# DAC.net
KiCad netlist of a schematic drawn in EAGLE
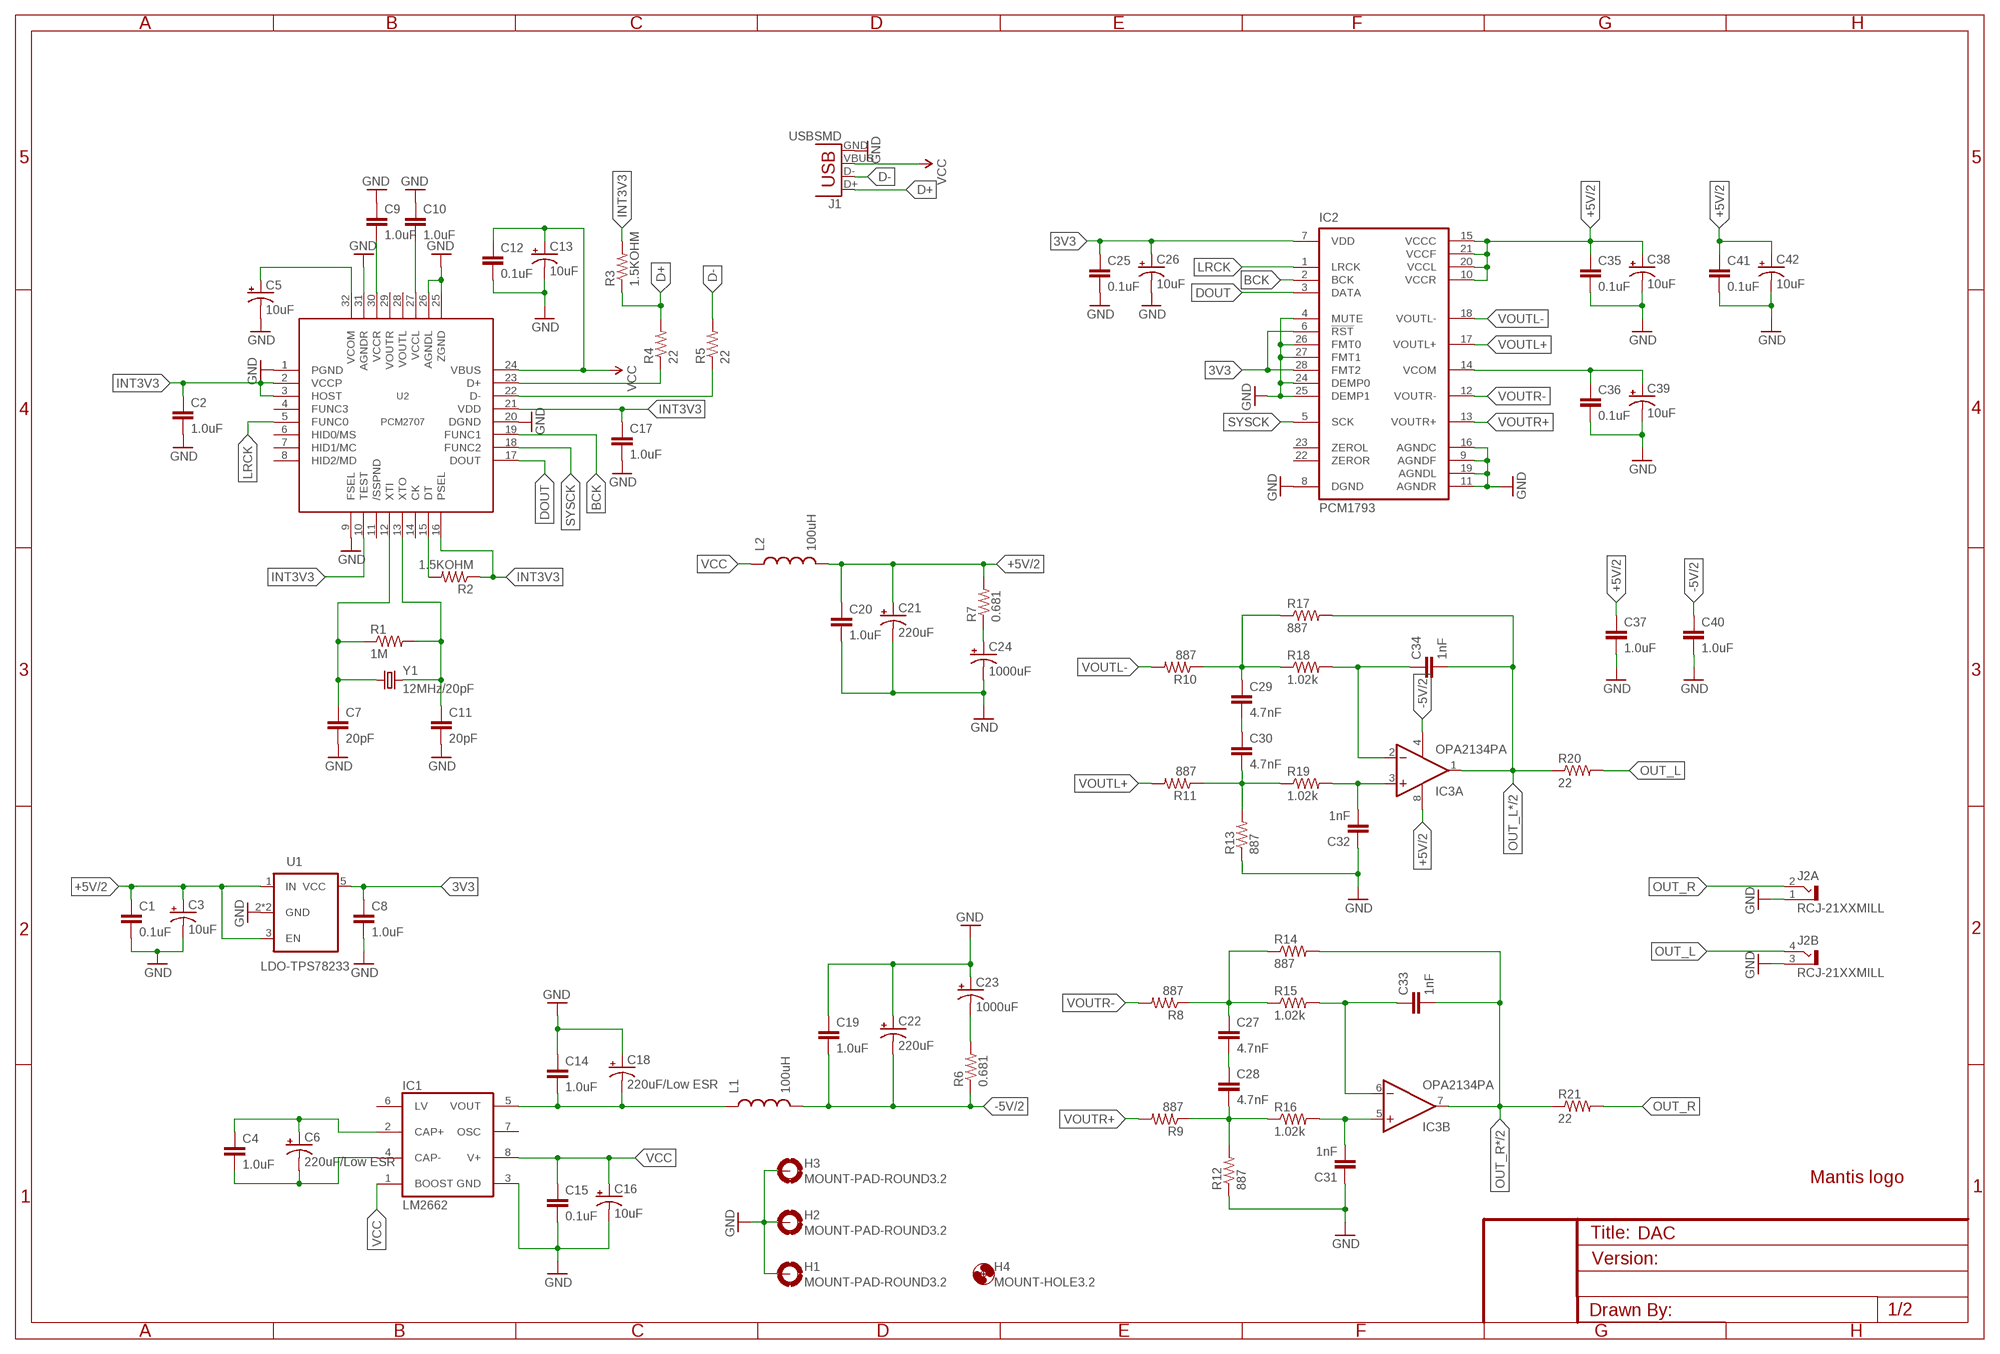
[diagram p0: schematic, sheet 1]
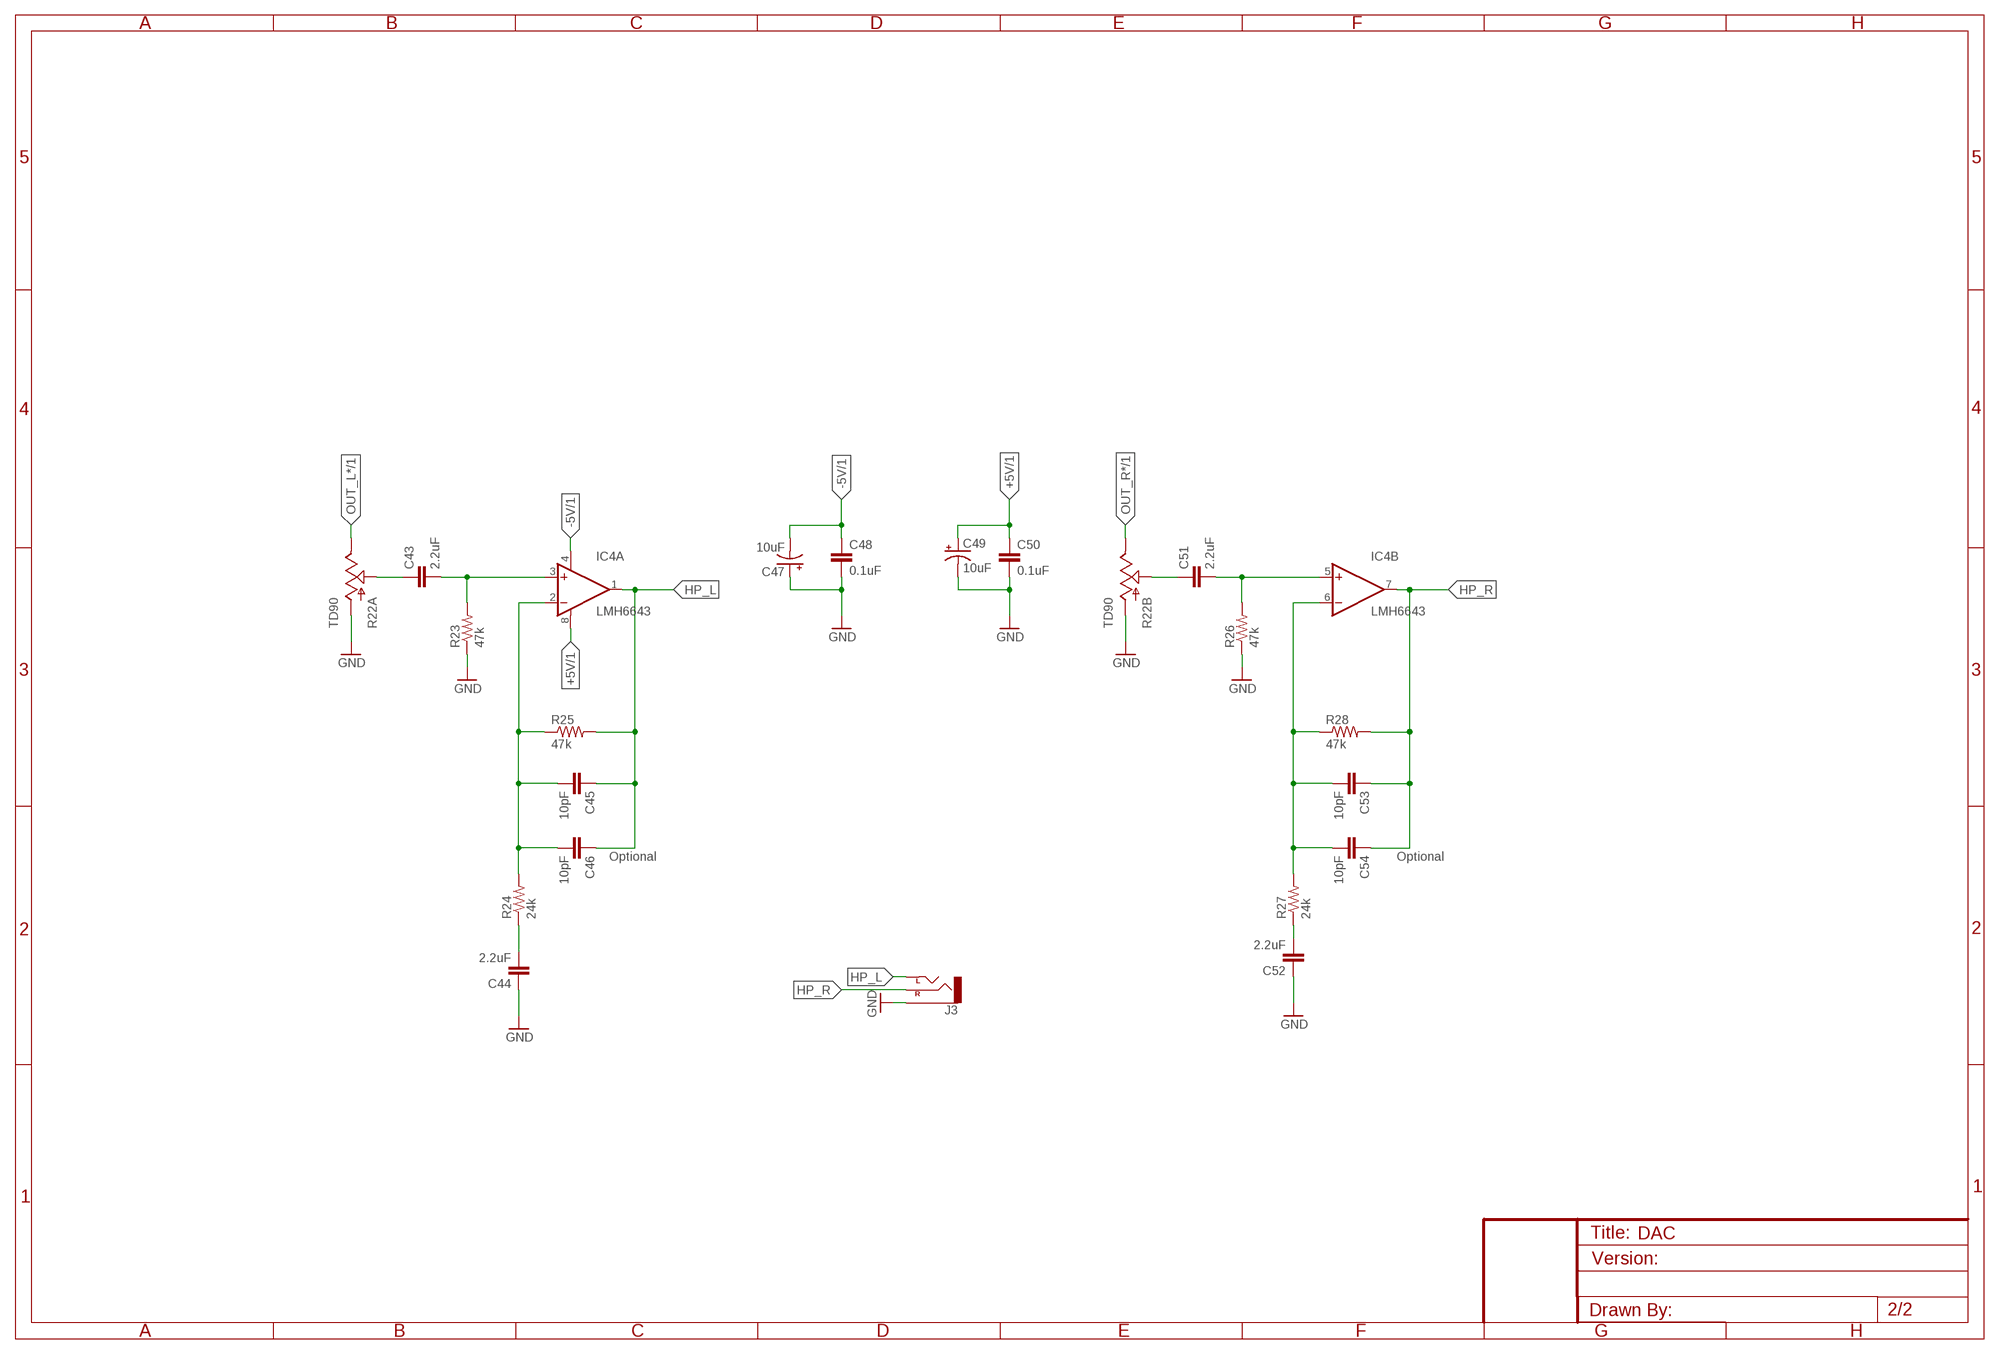
[diagram p1: schematic, sheet 2]

(export (version "E")
  (design (tool "Eeschema 10.0.6"))
  (components
    (comp (ref "C43")
      (value "2.2uF")
      (footprint "eagle-import:C5B5")
      (libsource (lib "eagle-import") (part "C5/5"))
    )
    (comp (ref "C44")
      (value "2.2uF")
      (footprint "eagle-import:C5B5")
      (libsource (lib "eagle-import") (part "C5/5"))
    )
    (comp (ref "C45")
      (value "10pF")
      (footprint "eagle-import:CAP-PTH-SMALL")
      (libsource (lib "eagle-import") (part "CAPPTH"))
    )
    (comp (ref "C46")
      (value "10pF")
      (footprint "eagle-import:0603-CAP")
      (libsource (lib "eagle-import") (part "10PF-50V-5%(0603)"))
    )
    (comp (ref "C47")
      (value "10uF")
      (footprint "eagle-import:CPOL-RADIAL-10UF-25V")
      (libsource (lib "eagle-import") (part "CAP_POLPTH2"))
    )
    (comp (ref "C48")
      (value "0.1uF")
      (footprint "eagle-import:0603-CAP")
      (libsource (lib "eagle-import") (part "1.0UF-16V-10%(0603)"))
    )
    (comp (ref "C49")
      (value "10uF")
      (footprint "eagle-import:CPOL-RADIAL-10UF-25V")
      (libsource (lib "eagle-import") (part "CAP_POLPTH2"))
    )
    (comp (ref "C50")
      (value "0.1uF")
      (footprint "eagle-import:0603-CAP")
      (libsource (lib "eagle-import") (part "1.0UF-16V-10%(0603)"))
    )
    (comp (ref "C51")
      (value "2.2uF")
      (footprint "eagle-import:C5B5")
      (libsource (lib "eagle-import") (part "C5/5"))
    )
    (comp (ref "C52")
      (value "2.2uF")
      (footprint "eagle-import:C5B5")
      (libsource (lib "eagle-import") (part "C5/5"))
    )
    (comp (ref "C53")
      (value "10pF")
      (footprint "eagle-import:CAP-PTH-SMALL")
      (libsource (lib "eagle-import") (part "CAPPTH"))
    )
    (comp (ref "C54")
      (value "10pF")
      (footprint "eagle-import:0603-CAP")
      (libsource (lib "eagle-import") (part "10PF-50V-5%(0603)"))
    )
    (comp (ref "IC4")
      (value "LMH6643")
      (footprint "eagle-import:SO08")
      (libsource (lib "eagle-import") (part "LMH6643"))
    )
    (comp (ref "J3")
      (value "AUDIO-JACKPTH")
      (footprint "eagle-import:AUDIO-JACK")
      (libsource (lib "eagle-import") (part "AUDIO-JACKPTH"))
    )
    (comp (ref "R22")
      (value "TD90")
      (footprint "eagle-import:PTD902")
      (libsource (lib "eagle-import") (part "TD90"))
    )
    (comp (ref "R23")
      (value "47k")
      (footprint "eagle-import:AXIAL-0.4")
      (libsource (lib "eagle-import") (part "RESISTORPTH-1/4W"))
    )
    (comp (ref "R24")
      (value "24k")
      (footprint "eagle-import:AXIAL-0.4")
      (libsource (lib "eagle-import") (part "RESISTORPTH-1/4W"))
    )
    (comp (ref "R25")
      (value "47k")
      (footprint "eagle-import:AXIAL-0.4")
      (libsource (lib "eagle-import") (part "RESISTORPTH-1/4W"))
    )
    (comp (ref "R26")
      (value "47k")
      (footprint "eagle-import:AXIAL-0.4")
      (libsource (lib "eagle-import") (part "RESISTORPTH-1/4W"))
    )
    (comp (ref "R27")
      (value "24k")
      (footprint "eagle-import:AXIAL-0.4")
      (libsource (lib "eagle-import") (part "RESISTORPTH-1/4W"))
    )
    (comp (ref "R28")
      (value "47k")
      (footprint "eagle-import:AXIAL-0.4")
      (libsource (lib "eagle-import") (part "RESISTORPTH-1/4W"))
    )
    (comp (ref "C1")
      (value "0.1uF")
      (footprint "eagle-import:0603-CAP")
      (libsource (lib "eagle-import") (part "0.1UF-25V-5%(0603)"))
    )
    (comp (ref "C2")
      (value "1.0uF")
      (footprint "eagle-import:0603-CAP")
      (libsource (lib "eagle-import") (part "1.0UF-16V-10%(0603)"))
    )
    (comp (ref "C3")
      (value "10uF")
      (footprint "eagle-import:CPOL-RADIAL-10UF-25V")
      (libsource (lib "eagle-import") (part "CAP_POLPTH2"))
    )
    (comp (ref "C4")
      (value "1.0uF")
      (footprint "eagle-import:0603-CAP")
      (libsource (lib "eagle-import") (part "1.0UF-16V-10%(0603)"))
    )
    (comp (ref "C5")
      (value "10uF")
      (footprint "eagle-import:CPOL-RADIAL-10UF-25V")
      (libsource (lib "eagle-import") (part "CAP_POLPTH2"))
    )
    (comp (ref "C6")
      (value "220uF/Low ESR")
      (footprint "eagle-import:CPOL-RADIAL-8_3.5")
      (libsource (lib "eagle-import") (part "CAP_POLPTH8MM"))
    )
    (comp (ref "C7")
      (value "20pF")
      (footprint "eagle-import:0603-CAP")
      (libsource (lib "eagle-import") (part "18PF-50V-5%(0603)"))
    )
    (comp (ref "C8")
      (value "1.0uF")
      (footprint "eagle-import:0805-CAP")
      (libsource (lib "eagle-import") (part "1.0UF-25V-+80/-20(0805){dblquote}"))
    )
    (comp (ref "C9")
      (value "1.0uF")
      (footprint "eagle-import:0603-CAP")
      (libsource (lib "eagle-import") (part "1.0UF-16V-10%(0603)"))
    )
    (comp (ref "C10")
      (value "1.0uF")
      (footprint "eagle-import:0603-CAP")
      (libsource (lib "eagle-import") (part "1.0UF-16V-10%(0603)"))
    )
    (comp (ref "C11")
      (value "20pF")
      (footprint "eagle-import:0603-CAP")
      (libsource (lib "eagle-import") (part "18PF-50V-5%(0603)"))
    )
    (comp (ref "C12")
      (value "0.1uF")
      (footprint "eagle-import:0603-CAP")
      (libsource (lib "eagle-import") (part "0.1UF-25V-5%(0603)"))
    )
    (comp (ref "C13")
      (value "10uF")
      (footprint "eagle-import:CPOL-RADIAL-10UF-25V")
      (libsource (lib "eagle-import") (part "CAP_POLPTH2"))
    )
    (comp (ref "C14")
      (value "1.0uF")
      (footprint "eagle-import:0603-CAP")
      (libsource (lib "eagle-import") (part "1.0UF-16V-10%(0603)"))
    )
    (comp (ref "C15")
      (value "0.1uF")
      (footprint "eagle-import:0603-CAP")
      (libsource (lib "eagle-import") (part "0.1UF-25V-5%(0603)"))
    )
    (comp (ref "C16")
      (value "10uF")
      (footprint "eagle-import:CPOL-RADIAL-10UF-25V")
      (libsource (lib "eagle-import") (part "CAP_POLPTH2"))
    )
    (comp (ref "C17")
      (value "1.0uF")
      (footprint "eagle-import:0603-CAP")
      (libsource (lib "eagle-import") (part "1.0UF-16V-10%(0603)"))
    )
    (comp (ref "C18")
      (value "220uF/Low ESR")
      (footprint "eagle-import:CPOL-RADIAL-8_3.5")
      (libsource (lib "eagle-import") (part "CAP_POLPTH8MM"))
    )
    (comp (ref "C19")
      (value "1.0uF")
      (footprint "eagle-import:0603-CAP")
      (libsource (lib "eagle-import") (part "1.0UF-16V-10%(0603)"))
    )
    (comp (ref "C20")
      (value "1.0uF")
      (footprint "eagle-import:0603-CAP")
      (libsource (lib "eagle-import") (part "1.0UF-16V-10%(0603)"))
    )
    (comp (ref "C21")
      (value "220uF")
      (footprint "eagle-import:CPOL-RADIAL-8_3.5")
      (libsource (lib "eagle-import") (part "CAP_POLPTH8MM"))
    )
    (comp (ref "C22")
      (value "220uF")
      (footprint "eagle-import:CPOL-RADIAL-8_3.5")
      (libsource (lib "eagle-import") (part "CAP_POLPTH8MM"))
    )
    (comp (ref "C23")
      (value "1000uF")
      (footprint "eagle-import:CPOL-RADIAL-1000UF-25V")
      (libsource (lib "eagle-import") (part "CAP_POLPTH4"))
    )
    (comp (ref "C24")
      (value "1000uF")
      (footprint "eagle-import:CPOL-RADIAL-1000UF-25V")
      (libsource (lib "eagle-import") (part "CAP_POLPTH4"))
    )
    (comp (ref "C25")
      (value "0.1uF")
      (footprint "eagle-import:0603-CAP")
      (libsource (lib "eagle-import") (part "0.1UF-25V-5%(0603)"))
    )
    (comp (ref "C26")
      (value "10uF")
      (footprint "eagle-import:CPOL-RADIAL-10UF-25V")
      (libsource (lib "eagle-import") (part "CAP_POLPTH2"))
    )
    (comp (ref "C27")
      (value "4.7nF")
      (footprint "eagle-import:C5B4.5")
      (libsource (lib "eagle-import") (part "C5/4.5"))
    )
    (comp (ref "C28")
      (value "4.7nF")
      (footprint "eagle-import:C5B4.5")
      (libsource (lib "eagle-import") (part "C5/4.5"))
    )
    (comp (ref "C29")
      (value "4.7nF")
      (footprint "eagle-import:C5B4.5")
      (libsource (lib "eagle-import") (part "C5/4.5"))
    )
    (comp (ref "C30")
      (value "4.7nF")
      (footprint "eagle-import:C5B4.5")
      (libsource (lib "eagle-import") (part "C5/4.5"))
    )
    (comp (ref "C31")
      (value "1nF")
      (footprint "eagle-import:C5B2.5")
      (libsource (lib "eagle-import") (part "C5/2.5"))
    )
    (comp (ref "C32")
      (value "1nF")
      (footprint "eagle-import:C5B2.5")
      (libsource (lib "eagle-import") (part "C5/2.5"))
    )
    (comp (ref "C33")
      (value "1nF")
      (footprint "eagle-import:C5B2.5")
      (libsource (lib "eagle-import") (part "C5/2.5"))
    )
    (comp (ref "C34")
      (value "1nF")
      (footprint "eagle-import:C5B2.5")
      (libsource (lib "eagle-import") (part "C5/2.5"))
    )
    (comp (ref "C35")
      (value "0.1uF")
      (footprint "eagle-import:0603-CAP")
      (libsource (lib "eagle-import") (part "0.1UF-25V-5%(0603)"))
    )
    (comp (ref "C36")
      (value "0.1uF")
      (footprint "eagle-import:0603-CAP")
      (libsource (lib "eagle-import") (part "0.1UF-25V-5%(0603)"))
    )
    (comp (ref "C37")
      (value "1.0uF")
      (footprint "eagle-import:0603-CAP")
      (libsource (lib "eagle-import") (part "1.0UF-16V-10%(0603)"))
    )
    (comp (ref "C38")
      (value "10uF")
      (footprint "eagle-import:CPOL-RADIAL-10UF-25V")
      (libsource (lib "eagle-import") (part "CAP_POLPTH2"))
    )
    (comp (ref "C39")
      (value "10uF")
      (footprint "eagle-import:CPOL-RADIAL-10UF-25V")
      (libsource (lib "eagle-import") (part "CAP_POLPTH2"))
    )
    (comp (ref "C40")
      (value "1.0uF")
      (footprint "eagle-import:0603-CAP")
      (libsource (lib "eagle-import") (part "1.0UF-16V-10%(0603)"))
    )
    (comp (ref "C41")
      (value "0.1uF")
      (footprint "eagle-import:0603-CAP")
      (libsource (lib "eagle-import") (part "0.1UF-25V-5%(0603)"))
    )
    (comp (ref "C42")
      (value "10uF")
      (footprint "eagle-import:CPOL-RADIAL-10UF-25V")
      (libsource (lib "eagle-import") (part "CAP_POLPTH2"))
    )
    (comp (ref "H1")
      (value "MOUNT-PAD-ROUND3.2")
      (footprint "eagle-import:3,2-PAD")
      (libsource (lib "eagle-import") (part "MOUNT-PAD-ROUND3.2"))
    )
    (comp (ref "H2")
      (value "MOUNT-PAD-ROUND3.2")
      (footprint "eagle-import:3,2-PAD")
      (libsource (lib "eagle-import") (part "MOUNT-PAD-ROUND3.2"))
    )
    (comp (ref "H3")
      (value "MOUNT-PAD-ROUND3.2")
      (footprint "eagle-import:3,2-PAD")
      (libsource (lib "eagle-import") (part "MOUNT-PAD-ROUND3.2"))
    )
    (comp (ref "H4")
      (value "MOUNT-HOLE3.2")
      (footprint "eagle-import:3,2")
      (libsource (lib "eagle-import") (part "MOUNT-HOLE3.2"))
    )
    (comp (ref "IC1")
      (value "LM2662")
      (footprint "eagle-import:SO08")
      (libsource (lib "eagle-import") (part "LM2662"))
    )
    (comp (ref "IC2")
      (value "PCM1793")
      (footprint "eagle-import:SSOP28BU")
      (fields (field (name "MF") "TEXAS INSTRUMENT CONNECTORS") (field (name "MPN") "PCM1793DBR"))
      (libsource (lib "eagle-import") (part "PCM1793"))
    )
    (comp (ref "IC3")
      (value "OPA2134PA")
      (footprint "eagle-import:DIL08")
      (libsource (lib "eagle-import") (part "OPA2PA134"))
    )
    (comp (ref "J1")
      (value "USBSMD")
      (footprint "eagle-import:USB-MINIB")
      (libsource (lib "eagle-import") (part "USBSMD"))
    )
    (comp (ref "J2")
      (value "RCJ-21XXMILL")
      (footprint "eagle-import:RCJ-21-MILL")
      (libsource (lib "eagle-import") (part "RCJ-21XXMILL"))
    )
    (comp (ref "L1")
      (value "100uH")
      (footprint "eagle-import:SRN6045")
      (libsource (lib "eagle-import") (part "INDUCTORBOURNS_SRN6045"))
    )
    (comp (ref "L2")
      (value "100uH")
      (footprint "eagle-import:SRN6045")
      (libsource (lib "eagle-import") (part "INDUCTORBOURNS_SRN6045"))
    )
    (comp (ref "LOGO1")
      (value "LOGO-MANTIS")
      (footprint "eagle-import:LOGO-MANTIS")
      (libsource (lib "eagle-import") (part "LOGO-MANTIS"))
    )
    (comp (ref "R1")
      (value "1M")
      (footprint "eagle-import:0603-RES")
      (libsource (lib "eagle-import") (part "1MOHM-1/10W-1%(0603)"))
    )
    (comp (ref "R2")
      (value "1.5KOHM")
      (footprint "eagle-import:0603")
      (libsource (lib "eagle-import") (part "1.5KOHM-1/10W-1%(0603)"))
    )
    (comp (ref "R3")
      (value "1.5KOHM")
      (footprint "eagle-import:0603")
      (libsource (lib "eagle-import") (part "1.5KOHM-1/10W-1%(0603)"))
    )
    (comp (ref "R4")
      (value "22")
      (footprint "eagle-import:0603-RES")
      (libsource (lib "eagle-import") (part "22OHM1/10W1%(0603)"))
    )
    (comp (ref "R5")
      (value "22")
      (footprint "eagle-import:0603-RES")
      (libsource (lib "eagle-import") (part "22OHM1/10W1%(0603)"))
    )
    (comp (ref "R6")
      (value "0.681")
      (footprint "eagle-import:0603-RES")
      (libsource (lib "eagle-import") (part "1OHM1/10W1%(0603)"))
    )
    (comp (ref "R7")
      (value "0.681")
      (footprint "eagle-import:0603-RES")
      (libsource (lib "eagle-import") (part "1OHM1/10W1%(0603)"))
    )
    (comp (ref "R8")
      (value "887")
      (footprint "eagle-import:AXIAL-0.4")
      (libsource (lib "eagle-import") (part "RESISTORPTH-1/4W"))
    )
    (comp (ref "R9")
      (value "887")
      (footprint "eagle-import:AXIAL-0.4")
      (libsource (lib "eagle-import") (part "RESISTORPTH-1/4W"))
    )
    (comp (ref "R10")
      (value "887")
      (footprint "eagle-import:AXIAL-0.4")
      (libsource (lib "eagle-import") (part "RESISTORPTH-1/4W"))
    )
    (comp (ref "R11")
      (value "887")
      (footprint "eagle-import:AXIAL-0.4")
      (libsource (lib "eagle-import") (part "RESISTORPTH-1/4W"))
    )
    (comp (ref "R12")
      (value "887")
      (footprint "eagle-import:AXIAL-0.4")
      (libsource (lib "eagle-import") (part "RESISTORPTH-1/4W"))
    )
    (comp (ref "R13")
      (value "887")
      (footprint "eagle-import:AXIAL-0.4")
      (libsource (lib "eagle-import") (part "RESISTORPTH-1/4W"))
    )
    (comp (ref "R14")
      (value "887")
      (footprint "eagle-import:AXIAL-0.4")
      (libsource (lib "eagle-import") (part "RESISTORPTH-1/4W"))
    )
    (comp (ref "R15")
      (value "1.02k")
      (footprint "eagle-import:AXIAL-0.4")
      (libsource (lib "eagle-import") (part "RESISTORPTH-1/4W"))
    )
    (comp (ref "R16")
      (value "1.02k")
      (footprint "eagle-import:AXIAL-0.4")
      (libsource (lib "eagle-import") (part "RESISTORPTH-1/4W"))
    )
    (comp (ref "R17")
      (value "887")
      (footprint "eagle-import:AXIAL-0.4")
      (libsource (lib "eagle-import") (part "RESISTORPTH-1/4W"))
    )
    (comp (ref "R18")
      (value "1.02k")
      (footprint "eagle-import:AXIAL-0.4")
      (libsource (lib "eagle-import") (part "RESISTORPTH-1/4W"))
    )
    (comp (ref "R19")
      (value "1.02k")
      (footprint "eagle-import:AXIAL-0.4")
      (libsource (lib "eagle-import") (part "RESISTORPTH-1/4W"))
    )
    (comp (ref "R20")
      (value "22")
      (footprint "eagle-import:AXIAL-0.4")
      (libsource (lib "eagle-import") (part "RESISTORPTH-1/4W"))
    )
    (comp (ref "R21")
      (value "22")
      (footprint "eagle-import:AXIAL-0.4")
      (libsource (lib "eagle-import") (part "RESISTORPTH-1/4W"))
    )
    (comp (ref "U1")
      (value "LDO-TPS78233")
      (footprint "eagle-import:SOT23-5")
      (libsource (lib "eagle-import") (part "LDO-TPS78233"))
    )
    (comp (ref "U2")
      (value "PCM2707")
      (footprint "eagle-import:TQFP32-08")
      (libsource (lib "eagle-import") (part "PCM2707"))
    )
    (comp (ref "Y1")
      (value "12MHz/20pF")
      (footprint "eagle-import:HC49US")
      (libsource (lib "eagle-import") (part "CRYSTALHC49US"))
    )
  )
  (nets
    (net (code "1") (name "+5V") (class "Default")
      (node (ref "C1") (pin "1") (pinfunction "1_1") (pintype "passive"))
      (node (ref "C20") (pin "1") (pinfunction "1_1") (pintype "passive"))
      (node (ref "C21") (pin "1") (pinfunction "+_1") (pintype "passive"))
      (node (ref "C3") (pin "1") (pinfunction "+_1") (pintype "passive"))
      (node (ref "C35") (pin "1") (pinfunction "1_1") (pintype "passive"))
      (node (ref "C37") (pin "1") (pinfunction "1_1") (pintype "passive"))
      (node (ref "C38") (pin "1") (pinfunction "+_1") (pintype "passive"))
      (node (ref "C41") (pin "1") (pinfunction "1_1") (pintype "passive"))
      (node (ref "C42") (pin "1") (pinfunction "+_1") (pintype "passive"))
      (node (ref "C49") (pin "1") (pinfunction "+_1") (pintype "passive"))
      (node (ref "C50") (pin "1") (pinfunction "1_1") (pintype "passive"))
      (node (ref "IC2") (pin "10") (pinfunction "VCCR_10") (pintype "power_in"))
      (node (ref "IC2") (pin "15") (pinfunction "VCCC_15") (pintype "power_in"))
      (node (ref "IC2") (pin "20") (pinfunction "VCCL_20") (pintype "power_in"))
      (node (ref "IC2") (pin "21") (pinfunction "VCCF_21") (pintype "power_in"))
      (node (ref "IC3") (pin "8") (pinfunction "V+_8") (pintype "power_in"))
      (node (ref "IC4") (pin "8") (pinfunction "V+_8") (pintype "power_in"))
      (node (ref "L2") (pin "2") (pinfunction "2_2") (pintype "passive"))
      (node (ref "R7") (pin "2") (pinfunction "2_2") (pintype "passive"))
      (node (ref "U1") (pin "1") (pinfunction "IN_1") (pintype "input"))
      (node (ref "U1") (pin "3") (pinfunction "EN_3") (pintype "input"))
    )
    (net (code "2") (name "-5V") (class "Default")
      (node (ref "C19") (pin "2") (pinfunction "2_2") (pintype "passive"))
      (node (ref "C22") (pin "2") (pinfunction "-_2") (pintype "passive"))
      (node (ref "C40") (pin "1") (pinfunction "1_1") (pintype "passive"))
      (node (ref "C47") (pin "2") (pinfunction "-_2") (pintype "passive"))
      (node (ref "C48") (pin "1") (pinfunction "1_1") (pintype "passive"))
      (node (ref "IC3") (pin "4") (pinfunction "V-_4") (pintype "power_in"))
      (node (ref "IC4") (pin "4") (pinfunction "V-_4") (pintype "power_in"))
      (node (ref "L1") (pin "2") (pinfunction "2_2") (pintype "passive"))
      (node (ref "R6") (pin "1") (pinfunction "1_1") (pintype "passive"))
    )
    (net (code "3") (name "3V3") (class "Default")
      (node (ref "C25") (pin "1") (pinfunction "1_1") (pintype "passive"))
      (node (ref "C26") (pin "1") (pinfunction "+_1") (pintype "passive"))
      (node (ref "C8") (pin "1") (pinfunction "1_1") (pintype "passive"))
      (node (ref "IC2") (pin "28") (pinfunction "FMT2_28") (pintype "input"))
      (node (ref "IC2") (pin "6") (pinfunction "~{RST}_6") (pintype "input"))
      (node (ref "IC2") (pin "7") (pinfunction "VDD_7") (pintype "power_in"))
      (node (ref "U1") (pin "5") (pinfunction "VCC_5") (pintype "power_in"))
    )
    (net (code "4") (name "BCK") (class "Default")
      (node (ref "IC2") (pin "2") (pinfunction "BCK_2") (pintype "input"))
      (node (ref "U2") (pin "19") (pinfunction "FUNC1_19") (pintype "bidirectional"))
    )
    (net (code "5") (name "D+") (class "Default")
      (node (ref "J1") (pin "D+") (pinfunction "D+_D+") (pintype "bidirectional"))
      (node (ref "R3") (pin "1") (pinfunction "1_1") (pintype "passive"))
      (node (ref "R4") (pin "2") (pinfunction "2_2") (pintype "passive"))
    )
    (net (code "6") (name "D-") (class "Default")
      (node (ref "J1") (pin "D-") (pinfunction "D-_D-") (pintype "bidirectional"))
      (node (ref "R5") (pin "2") (pinfunction "2_2") (pintype "passive"))
    )
    (net (code "7") (name "DOUT") (class "Default")
      (node (ref "IC2") (pin "3") (pinfunction "DATA_3") (pintype "input"))
      (node (ref "U2") (pin "17") (pinfunction "DOUT_17") (pintype "bidirectional"))
    )
    (net (code "8") (name "GND") (class "Default")
      (node (ref "C1") (pin "2") (pinfunction "2_2") (pintype "passive"))
      (node (ref "C10") (pin "1") (pinfunction "1_1") (pintype "passive"))
      (node (ref "C11") (pin "2") (pinfunction "2_2") (pintype "passive"))
      (node (ref "C12") (pin "2") (pinfunction "2_2") (pintype "passive"))
      (node (ref "C13") (pin "2") (pinfunction "-_2") (pintype "passive"))
      (node (ref "C14") (pin "1") (pinfunction "1_1") (pintype "passive"))
      (node (ref "C15") (pin "2") (pinfunction "2_2") (pintype "passive"))
      (node (ref "C16") (pin "2") (pinfunction "-_2") (pintype "passive"))
      (node (ref "C17") (pin "2") (pinfunction "2_2") (pintype "passive"))
      (node (ref "C18") (pin "1") (pinfunction "+_1") (pintype "passive"))
      (node (ref "C19") (pin "1") (pinfunction "1_1") (pintype "passive"))
      (node (ref "C2") (pin "2") (pinfunction "2_2") (pintype "passive"))
      (node (ref "C20") (pin "2") (pinfunction "2_2") (pintype "passive"))
      (node (ref "C21") (pin "2") (pinfunction "-_2") (pintype "passive"))
      (node (ref "C22") (pin "1") (pinfunction "+_1") (pintype "passive"))
      (node (ref "C23") (pin "+") (pinfunction "+_+") (pintype "passive"))
      (node (ref "C24") (pin "-") (pinfunction "-_-") (pintype "passive"))
      (node (ref "C25") (pin "2") (pinfunction "2_2") (pintype "passive"))
      (node (ref "C26") (pin "2") (pinfunction "-_2") (pintype "passive"))
      (node (ref "C3") (pin "2") (pinfunction "-_2") (pintype "passive"))
      (node (ref "C31") (pin "1") (pinfunction "1_1") (pintype "passive"))
      (node (ref "C32") (pin "1") (pinfunction "1_1") (pintype "passive"))
      (node (ref "C35") (pin "2") (pinfunction "2_2") (pintype "passive"))
      (node (ref "C36") (pin "2") (pinfunction "2_2") (pintype "passive"))
      (node (ref "C37") (pin "2") (pinfunction "2_2") (pintype "passive"))
      (node (ref "C38") (pin "2") (pinfunction "-_2") (pintype "passive"))
      (node (ref "C39") (pin "2") (pinfunction "-_2") (pintype "passive"))
      (node (ref "C40") (pin "2") (pinfunction "2_2") (pintype "passive"))
      (node (ref "C41") (pin "2") (pinfunction "2_2") (pintype "passive"))
      (node (ref "C42") (pin "2") (pinfunction "-_2") (pintype "passive"))
      (node (ref "C44") (pin "1") (pinfunction "1_1") (pintype "passive"))
      (node (ref "C47") (pin "1") (pinfunction "+_1") (pintype "passive"))
      (node (ref "C48") (pin "2") (pinfunction "2_2") (pintype "passive"))
      (node (ref "C49") (pin "2") (pinfunction "-_2") (pintype "passive"))
      (node (ref "C5") (pin "2") (pinfunction "-_2") (pintype "passive"))
      (node (ref "C50") (pin "2") (pinfunction "2_2") (pintype "passive"))
      (node (ref "C52") (pin "1") (pinfunction "1_1") (pintype "passive"))
      (node (ref "C7") (pin "2") (pinfunction "2_2") (pintype "passive"))
      (node (ref "C8") (pin "2") (pinfunction "2_2") (pintype "passive"))
      (node (ref "C9") (pin "1") (pinfunction "1_1") (pintype "passive"))
      (node (ref "H1") (pin "B3,2") (pinfunction "MOUNT_B3,2") (pintype "passive"))
      (node (ref "H2") (pin "B3,2") (pinfunction "MOUNT_B3,2") (pintype "passive"))
      (node (ref "H3") (pin "B3,2") (pinfunction "MOUNT_B3,2") (pintype "passive"))
      (node (ref "IC1") (pin "3") (pinfunction "GND_3") (pintype "power_in"))
      (node (ref "IC2") (pin "11") (pinfunction "AGNDR_11") (pintype "power_in"))
      (node (ref "IC2") (pin "16") (pinfunction "AGNDC_16") (pintype "power_in"))
      (node (ref "IC2") (pin "19") (pinfunction "AGNDL_19") (pintype "power_in"))
      (node (ref "IC2") (pin "24") (pinfunction "DEMP0_24") (pintype "input"))
      (node (ref "IC2") (pin "25") (pinfunction "DEMP1_25") (pintype "input"))
      (node (ref "IC2") (pin "26") (pinfunction "FMT0_26") (pintype "input"))
      (node (ref "IC2") (pin "27") (pinfunction "FMT1_27") (pintype "input"))
      (node (ref "IC2") (pin "4") (pinfunction "MUTE_4") (pintype "input"))
      (node (ref "IC2") (pin "8") (pinfunction "DGND_8") (pintype "power_in"))
      (node (ref "IC2") (pin "9") (pinfunction "AGNDF_9") (pintype "power_in"))
      (node (ref "J1") (pin "GND") (pinfunction "GND_GND") (pintype "bidirectional"))
      (node (ref "J2") (pin "1") (pinfunction "S_1") (pintype "passive"))
      (node (ref "J2") (pin "3") (pinfunction "S_3") (pintype "passive"))
      (node (ref "J3") (pin "SLEEVE") (pinfunction "SLEEVE_SLEEVE") (pintype "bidirectional"))
      (node (ref "R12") (pin "P$1") (pinfunction "1_P$1") (pintype "passive"))
      (node (ref "R13") (pin "P$1") (pinfunction "1_P$1") (pintype "passive"))
      (node (ref "R22") (pin "R1.1") (pinfunction "A_R1.1") (pintype "passive"))
      (node (ref "R22") (pin "R2.1") (pinfunction "A_R2.1") (pintype "passive"))
      (node (ref "R23") (pin "P$1") (pinfunction "1_P$1") (pintype "passive"))
      (node (ref "R26") (pin "P$1") (pinfunction "1_P$1") (pintype "passive"))
      (node (ref "U1") (pin "2") (pinfunction "GND_2") (pintype "input"))
      (node (ref "U1") (pin "4") (pinfunction "GND_4") (pintype "input"))
      (node (ref "U2") (pin "1") (pinfunction "PGND_1") (pintype "bidirectional"))
      (node (ref "U2") (pin "20") (pinfunction "DGND_20") (pintype "bidirectional"))
      (node (ref "U2") (pin "25") (pinfunction "ZGND_25") (pintype "bidirectional"))
      (node (ref "U2") (pin "26") (pinfunction "AGNDL_26") (pintype "bidirectional"))
      (node (ref "U2") (pin "31") (pinfunction "AGNDR_31") (pintype "bidirectional"))
      (node (ref "U2") (pin "9") (pinfunction "FSEL_9") (pintype "bidirectional"))
    )
    (net (code "9") (name "HP_L") (class "Default")
      (node (ref "C45") (pin "1") (pinfunction "1_1") (pintype "passive"))
      (node (ref "C46") (pin "1") (pinfunction "1_1") (pintype "passive"))
      (node (ref "IC4") (pin "1") (pinfunction "OUT_1") (pintype "output"))
      (node (ref "J3") (pin "TIP") (pinfunction "LEFT_TIP") (pintype "bidirectional"))
      (node (ref "R25") (pin "P$2") (pinfunction "2_P$2") (pintype "passive"))
    )
    (net (code "10") (name "HP_R") (class "Default")
      (node (ref "C53") (pin "1") (pinfunction "1_1") (pintype "passive"))
      (node (ref "C54") (pin "1") (pinfunction "1_1") (pintype "passive"))
      (node (ref "IC4") (pin "7") (pinfunction "OUT_7") (pintype "output"))
      (node (ref "J3") (pin "RING") (pinfunction "RIGHT_RING") (pintype "bidirectional"))
      (node (ref "R28") (pin "P$2") (pinfunction "2_P$2") (pintype "passive"))
    )
    (net (code "11") (name "INT3V3") (class "Default")
      (node (ref "C17") (pin "1") (pinfunction "1_1") (pintype "passive"))
      (node (ref "C2") (pin "1") (pinfunction "1_1") (pintype "passive"))
      (node (ref "R2") (pin "1") (pinfunction "1_1") (pintype "passive"))
      (node (ref "R3") (pin "2") (pinfunction "2_2") (pintype "passive"))
      (node (ref "U2") (pin "10") (pinfunction "TEST_10") (pintype "bidirectional"))
      (node (ref "U2") (pin "16") (pinfunction "PSEL_16") (pintype "bidirectional"))
      (node (ref "U2") (pin "2") (pinfunction "VCCP_2") (pintype "bidirectional"))
      (node (ref "U2") (pin "21") (pinfunction "VDD_21") (pintype "bidirectional"))
      (node (ref "U2") (pin "3") (pinfunction "HOST_3") (pintype "bidirectional"))
    )
    (net (code "12") (name "LRCK") (class "Default")
      (node (ref "IC2") (pin "1") (pinfunction "LRCK_1") (pintype "input"))
      (node (ref "U2") (pin "5") (pinfunction "FUNC0_5") (pintype "bidirectional"))
    )
    (net (code "13") (name "Net-(C5-+)") (class "Default")
      (node (ref "C5") (pin "1") (pinfunction "+_1") (pintype "passive"))
      (node (ref "U2") (pin "32") (pinfunction "VCOM_32") (pintype "bidirectional"))
    )
    (net (code "14") (name "Net-(C6-+)") (class "Default")
      (node (ref "C4") (pin "1") (pinfunction "1_1") (pintype "passive"))
      (node (ref "C6") (pin "1") (pinfunction "+_1") (pintype "passive"))
      (node (ref "IC1") (pin "2") (pinfunction "CAP+_2") (pintype "passive"))
    )
    (net (code "15") (name "Net-(C6--)") (class "Default")
      (node (ref "C4") (pin "2") (pinfunction "2_2") (pintype "passive"))
      (node (ref "C6") (pin "2") (pinfunction "-_2") (pintype "passive"))
      (node (ref "IC1") (pin "4") (pinfunction "CAP-_4") (pintype "passive"))
    )
    (net (code "16") (name "Net-(C18--)") (class "Default")
      (node (ref "C14") (pin "2") (pinfunction "2_2") (pintype "passive"))
      (node (ref "C18") (pin "2") (pinfunction "-_2") (pintype "passive"))
      (node (ref "IC1") (pin "5") (pinfunction "VOUT_5") (pintype "output"))
      (node (ref "L1") (pin "1") (pinfunction "1_1") (pintype "passive"))
    )
    (net (code "17") (name "Net-(C23-Pad-)") (class "Default")
      (node (ref "C23") (pin "-") (pinfunction "-_-") (pintype "passive"))
      (node (ref "R6") (pin "2") (pinfunction "2_2") (pintype "passive"))
    )
    (net (code "18") (name "Net-(C24-Pad+)") (class "Default")
      (node (ref "C24") (pin "+") (pinfunction "+_+") (pintype "passive"))
      (node (ref "R7") (pin "1") (pinfunction "1_1") (pintype "passive"))
    )
    (net (code "19") (name "Net-(C27-Pad2)") (class "Default")
      (node (ref "C27") (pin "2") (pinfunction "2_2") (pintype "passive"))
      (node (ref "C28") (pin "1") (pinfunction "1_1") (pintype "passive"))
    )
    (net (code "20") (name "Net-(C29-Pad2)") (class "Default")
      (node (ref "C29") (pin "2") (pinfunction "2_2") (pintype "passive"))
      (node (ref "C30") (pin "1") (pinfunction "1_1") (pintype "passive"))
    )
    (net (code "21") (name "Net-(C39-+)") (class "Default")
      (node (ref "C36") (pin "1") (pinfunction "1_1") (pintype "passive"))
      (node (ref "C39") (pin "1") (pinfunction "+_1") (pintype "passive"))
      (node (ref "IC2") (pin "14") (pinfunction "VCOM_14") (pintype "passive"))
    )
    (net (code "22") (name "Net-(IC3A-+IN)") (class "Default")
      (node (ref "C32") (pin "2") (pinfunction "2_2") (pintype "passive"))
      (node (ref "IC3") (pin "3") (pinfunction "+IN_3") (pintype "input"))
      (node (ref "R19") (pin "P$2") (pinfunction "2_P$2") (pintype "passive"))
    )
    (net (code "23") (name "Net-(IC3A--IN)") (class "Default")
      (node (ref "C34") (pin "1") (pinfunction "1_1") (pintype "passive"))
      (node (ref "IC3") (pin "2") (pinfunction "-IN_2") (pintype "input"))
      (node (ref "R18") (pin "P$2") (pinfunction "2_P$2") (pintype "passive"))
    )
    (net (code "24") (name "Net-(IC3B-+IN)") (class "Default")
      (node (ref "C31") (pin "2") (pinfunction "2_2") (pintype "passive"))
      (node (ref "IC3") (pin "5") (pinfunction "+IN_5") (pintype "input"))
      (node (ref "R16") (pin "P$2") (pinfunction "2_P$2") (pintype "passive"))
    )
    (net (code "25") (name "Net-(IC3B--IN)") (class "Default")
      (node (ref "C33") (pin "1") (pinfunction "1_1") (pintype "passive"))
      (node (ref "IC3") (pin "6") (pinfunction "-IN_6") (pintype "input"))
      (node (ref "R15") (pin "P$2") (pinfunction "2_P$2") (pintype "passive"))
    )
    (net (code "26") (name "Net-(IC4A-+IN)") (class "Default")
      (node (ref "C43") (pin "2") (pinfunction "2_2") (pintype "passive"))
      (node (ref "IC4") (pin "3") (pinfunction "+IN_3") (pintype "input"))
      (node (ref "R23") (pin "P$2") (pinfunction "2_P$2") (pintype "passive"))
    )
    (net (code "27") (name "Net-(IC4A--IN)") (class "Default")
      (node (ref "C45") (pin "2") (pinfunction "2_2") (pintype "passive"))
      (node (ref "C46") (pin "2") (pinfunction "2_2") (pintype "passive"))
      (node (ref "IC4") (pin "2") (pinfunction "-IN_2") (pintype "input"))
      (node (ref "R24") (pin "P$2") (pinfunction "2_P$2") (pintype "passive"))
      (node (ref "R25") (pin "P$1") (pinfunction "1_P$1") (pintype "passive"))
    )
    (net (code "28") (name "Net-(IC4B-+IN)") (class "Default")
      (node (ref "C51") (pin "2") (pinfunction "2_2") (pintype "passive"))
      (node (ref "IC4") (pin "5") (pinfunction "+IN_5") (pintype "input"))
      (node (ref "R26") (pin "P$2") (pinfunction "2_P$2") (pintype "passive"))
    )
    (net (code "29") (name "Net-(IC4B--IN)") (class "Default")
      (node (ref "C53") (pin "2") (pinfunction "2_2") (pintype "passive"))
      (node (ref "C54") (pin "2") (pinfunction "2_2") (pintype "passive"))
      (node (ref "IC4") (pin "6") (pinfunction "-IN_6") (pintype "input"))
      (node (ref "R27") (pin "P$2") (pinfunction "2_P$2") (pintype "passive"))
      (node (ref "R28") (pin "P$1") (pinfunction "1_P$1") (pintype "passive"))
    )
    (net (code "30") (name "Net-(R10-1)") (class "Default")
      (node (ref "C29") (pin "1") (pinfunction "1_1") (pintype "passive"))
      (node (ref "R10") (pin "P$1") (pinfunction "1_P$1") (pintype "passive"))
      (node (ref "R17") (pin "P$1") (pinfunction "1_P$1") (pintype "passive"))
      (node (ref "R18") (pin "P$1") (pinfunction "1_P$1") (pintype "passive"))
    )
    (net (code "31") (name "Net-(R11-1)") (class "Default")
      (node (ref "C30") (pin "2") (pinfunction "2_2") (pintype "passive"))
      (node (ref "R11") (pin "P$1") (pinfunction "1_P$1") (pintype "passive"))
      (node (ref "R13") (pin "P$2") (pinfunction "2_P$2") (pintype "passive"))
      (node (ref "R19") (pin "P$1") (pinfunction "1_P$1") (pintype "passive"))
    )
    (net (code "32") (name "Net-(R12-2)") (class "Default")
      (node (ref "C28") (pin "2") (pinfunction "2_2") (pintype "passive"))
      (node (ref "R12") (pin "P$2") (pinfunction "2_P$2") (pintype "passive"))
      (node (ref "R16") (pin "P$1") (pinfunction "1_P$1") (pintype "passive"))
      (node (ref "R9") (pin "P$1") (pinfunction "1_P$1") (pintype "passive"))
    )
    (net (code "33") (name "Net-(R14-1)") (class "Default")
      (node (ref "C27") (pin "1") (pinfunction "1_1") (pintype "passive"))
      (node (ref "R14") (pin "P$1") (pinfunction "1_P$1") (pintype "passive"))
      (node (ref "R15") (pin "P$1") (pinfunction "1_P$1") (pintype "passive"))
      (node (ref "R8") (pin "P$1") (pinfunction "1_P$1") (pintype "passive"))
    )
    (net (code "34") (name "Net-(R22A-S)") (class "Default")
      (node (ref "C43") (pin "1") (pinfunction "1_1") (pintype "passive"))
      (node (ref "R22") (pin "R1.2") (pinfunction "S_R1.2") (pintype "passive"))
    )
    (net (code "35") (name "Net-(R22B-S)") (class "Default")
      (node (ref "C51") (pin "1") (pinfunction "1_1") (pintype "passive"))
      (node (ref "R22") (pin "R2.2") (pinfunction "S_R2.2") (pintype "passive"))
    )
    (net (code "36") (name "Net-(R24-1)") (class "Default")
      (node (ref "C44") (pin "2") (pinfunction "2_2") (pintype "passive"))
      (node (ref "R24") (pin "P$1") (pinfunction "1_P$1") (pintype "passive"))
    )
    (net (code "37") (name "Net-(R27-1)") (class "Default")
      (node (ref "C52") (pin "2") (pinfunction "2_2") (pintype "passive"))
      (node (ref "R27") (pin "P$1") (pinfunction "1_P$1") (pintype "passive"))
    )
    (net (code "38") (name "Net-(U2-D+)") (class "Default")
      (node (ref "R4") (pin "1") (pinfunction "1_1") (pintype "passive"))
      (node (ref "U2") (pin "23") (pinfunction "D+_23") (pintype "bidirectional"))
    )
    (net (code "39") (name "Net-(U2-D-)") (class "Default")
      (node (ref "R5") (pin "1") (pinfunction "1_1") (pintype "passive"))
      (node (ref "U2") (pin "22") (pinfunction "D-_22") (pintype "bidirectional"))
    )
    (net (code "40") (name "Net-(U2-DT)") (class "Default")
      (node (ref "R2") (pin "2") (pinfunction "2_2") (pintype "passive"))
      (node (ref "U2") (pin "15") (pinfunction "DT_15") (pintype "bidirectional"))
    )
    (net (code "41") (name "Net-(U2-VCCL)") (class "Default")
      (node (ref "C10") (pin "2") (pinfunction "2_2") (pintype "passive"))
      (node (ref "U2") (pin "27") (pinfunction "VCCL_27") (pintype "bidirectional"))
    )
    (net (code "42") (name "Net-(U2-VCCR)") (class "Default")
      (node (ref "C9") (pin "2") (pinfunction "2_2") (pintype "passive"))
      (node (ref "U2") (pin "30") (pinfunction "VCCR_30") (pintype "bidirectional"))
    )
    (net (code "43") (name "Net-(U2-XTI)") (class "Default")
      (node (ref "C7") (pin "1") (pinfunction "1_1") (pintype "passive"))
      (node (ref "R1") (pin "1") (pinfunction "1_1") (pintype "passive"))
      (node (ref "U2") (pin "12") (pinfunction "XTI_12") (pintype "bidirectional"))
      (node (ref "Y1") (pin "1") (pinfunction "1_1") (pintype "passive"))
    )
    (net (code "44") (name "Net-(U2-XTO)") (class "Default")
      (node (ref "C11") (pin "1") (pinfunction "1_1") (pintype "passive"))
      (node (ref "R1") (pin "2") (pinfunction "2_2") (pintype "passive"))
      (node (ref "U2") (pin "13") (pinfunction "XTO_13") (pintype "bidirectional"))
      (node (ref "Y1") (pin "2") (pinfunction "2_2") (pintype "passive"))
    )
    (net (code "45") (name "OUT_L") (class "Default")
      (node (ref "J2") (pin "4") (pinfunction "T_4") (pintype "passive"))
      (node (ref "R20") (pin "P$2") (pinfunction "2_P$2") (pintype "passive"))
    )
    (net (code "46") (name "OUT_L*") (class "Default")
      (node (ref "C34") (pin "2") (pinfunction "2_2") (pintype "passive"))
      (node (ref "IC3") (pin "1") (pinfunction "OUT_1") (pintype "output"))
      (node (ref "R17") (pin "P$2") (pinfunction "2_P$2") (pintype "passive"))
      (node (ref "R20") (pin "P$1") (pinfunction "1_P$1") (pintype "passive"))
      (node (ref "R22") (pin "R1.3") (pinfunction "E_R1.3") (pintype "passive"))
    )
    (net (code "47") (name "OUT_R") (class "Default")
      (node (ref "J2") (pin "2") (pinfunction "T_2") (pintype "passive"))
      (node (ref "R21") (pin "P$2") (pinfunction "2_P$2") (pintype "passive"))
    )
    (net (code "48") (name "OUT_R*") (class "Default")
      (node (ref "C33") (pin "2") (pinfunction "2_2") (pintype "passive"))
      (node (ref "IC3") (pin "7") (pinfunction "OUT_7") (pintype "output"))
      (node (ref "R14") (pin "P$2") (pinfunction "2_P$2") (pintype "passive"))
      (node (ref "R21") (pin "P$1") (pinfunction "1_P$1") (pintype "passive"))
      (node (ref "R22") (pin "R2.3") (pinfunction "E_R2.3") (pintype "passive"))
    )
    (net (code "49") (name "SYSCK") (class "Default")
      (node (ref "IC2") (pin "5") (pinfunction "SCK_5") (pintype "input"))
      (node (ref "U2") (pin "18") (pinfunction "FUNC2_18") (pintype "bidirectional"))
    )
    (net (code "50") (name "VCC") (class "Default")
      (node (ref "C12") (pin "1") (pinfunction "1_1") (pintype "passive"))
      (node (ref "C13") (pin "1") (pinfunction "+_1") (pintype "passive"))
      (node (ref "C15") (pin "1") (pinfunction "1_1") (pintype "passive"))
      (node (ref "C16") (pin "1") (pinfunction "+_1") (pintype "passive"))
      (node (ref "IC1") (pin "1") (pinfunction "BOOST_1") (pintype "input"))
      (node (ref "IC1") (pin "8") (pinfunction "V+_8") (pintype "power_in"))
      (node (ref "J1") (pin "VBUS") (pinfunction "VBUS_VBUS") (pintype "bidirectional"))
      (node (ref "L2") (pin "1") (pinfunction "1_1") (pintype "passive"))
      (node (ref "U2") (pin "24") (pinfunction "VBUS_24") (pintype "bidirectional"))
    )
    (net (code "51") (name "VOUTL+") (class "Default")
      (node (ref "IC2") (pin "17") (pinfunction "VOUTL+_17") (pintype "output"))
      (node (ref "R11") (pin "P$2") (pinfunction "2_P$2") (pintype "passive"))
    )
    (net (code "52") (name "VOUTL-") (class "Default")
      (node (ref "IC2") (pin "18") (pinfunction "VOUTL-_18") (pintype "output"))
      (node (ref "R10") (pin "P$2") (pinfunction "2_P$2") (pintype "passive"))
    )
    (net (code "53") (name "VOUTR+") (class "Default")
      (node (ref "IC2") (pin "13") (pinfunction "VOUTR+_13") (pintype "output"))
      (node (ref "R9") (pin "P$2") (pinfunction "2_P$2") (pintype "passive"))
    )
    (net (code "54") (name "VOUTR-") (class "Default")
      (node (ref "IC2") (pin "12") (pinfunction "VOUTR-_12") (pintype "output"))
      (node (ref "R8") (pin "P$2") (pinfunction "2_P$2") (pintype "passive"))
    )
    (net (code "55") (name "unconnected-(IC1-LV-Pad6)") (class "Default")
      (node (ref "IC1") (pin "6") (pinfunction "LV_6") (pintype "passive"))
    )
    (net (code "56") (name "unconnected-(IC1-OSC-Pad7)") (class "Default")
      (node (ref "IC1") (pin "7") (pinfunction "OSC_7") (pintype "output"))
    )
    (net (code "57") (name "unconnected-(IC2-ZEROL-Pad23)") (class "Default")
      (node (ref "IC2") (pin "23") (pinfunction "ZEROL_23") (pintype "output"))
    )
    (net (code "58") (name "unconnected-(IC2-ZEROR-Pad22)") (class "Default")
      (node (ref "IC2") (pin "22") (pinfunction "ZEROR_22") (pintype "output"))
    )
    (net (code "59") (name "unconnected-(U2-CK-Pad14)") (class "Default")
      (node (ref "U2") (pin "14") (pinfunction "CK_14") (pintype "bidirectional"))
    )
    (net (code "60") (name "unconnected-(U2-FUNC3-Pad4)") (class "Default")
      (node (ref "U2") (pin "4") (pinfunction "FUNC3_4") (pintype "bidirectional"))
    )
    (net (code "61") (name "unconnected-(U2-HID0{slash}MS-Pad6)") (class "Default")
      (node (ref "U2") (pin "6") (pinfunction "HID0/MS_6") (pintype "bidirectional"))
    )
    (net (code "62") (name "unconnected-(U2-HID1{slash}MC-Pad7)") (class "Default")
      (node (ref "U2") (pin "7") (pinfunction "HID1/MC_7") (pintype "bidirectional"))
    )
    (net (code "63") (name "unconnected-(U2-HID2{slash}MD-Pad8)") (class "Default")
      (node (ref "U2") (pin "8") (pinfunction "HID2/MD_8") (pintype "bidirectional"))
    )
    (net (code "64") (name "unconnected-(U2-VOUTL-Pad28)") (class "Default")
      (node (ref "U2") (pin "28") (pinfunction "VOUTL_28") (pintype "bidirectional"))
    )
    (net (code "65") (name "unconnected-(U2-VOUTR-Pad29)") (class "Default")
      (node (ref "U2") (pin "29") (pinfunction "VOUTR_29") (pintype "bidirectional"))
    )
    (net (code "66") (name "unconnected-(U2-{slash}SSPND-Pad11)") (class "Default")
      (node (ref "U2") (pin "11") (pinfunction "/SSPND_11") (pintype "bidirectional"))
    )
  )
)
